# H09R0.net
KiCad netlist of a schematic drawn in EAGLE
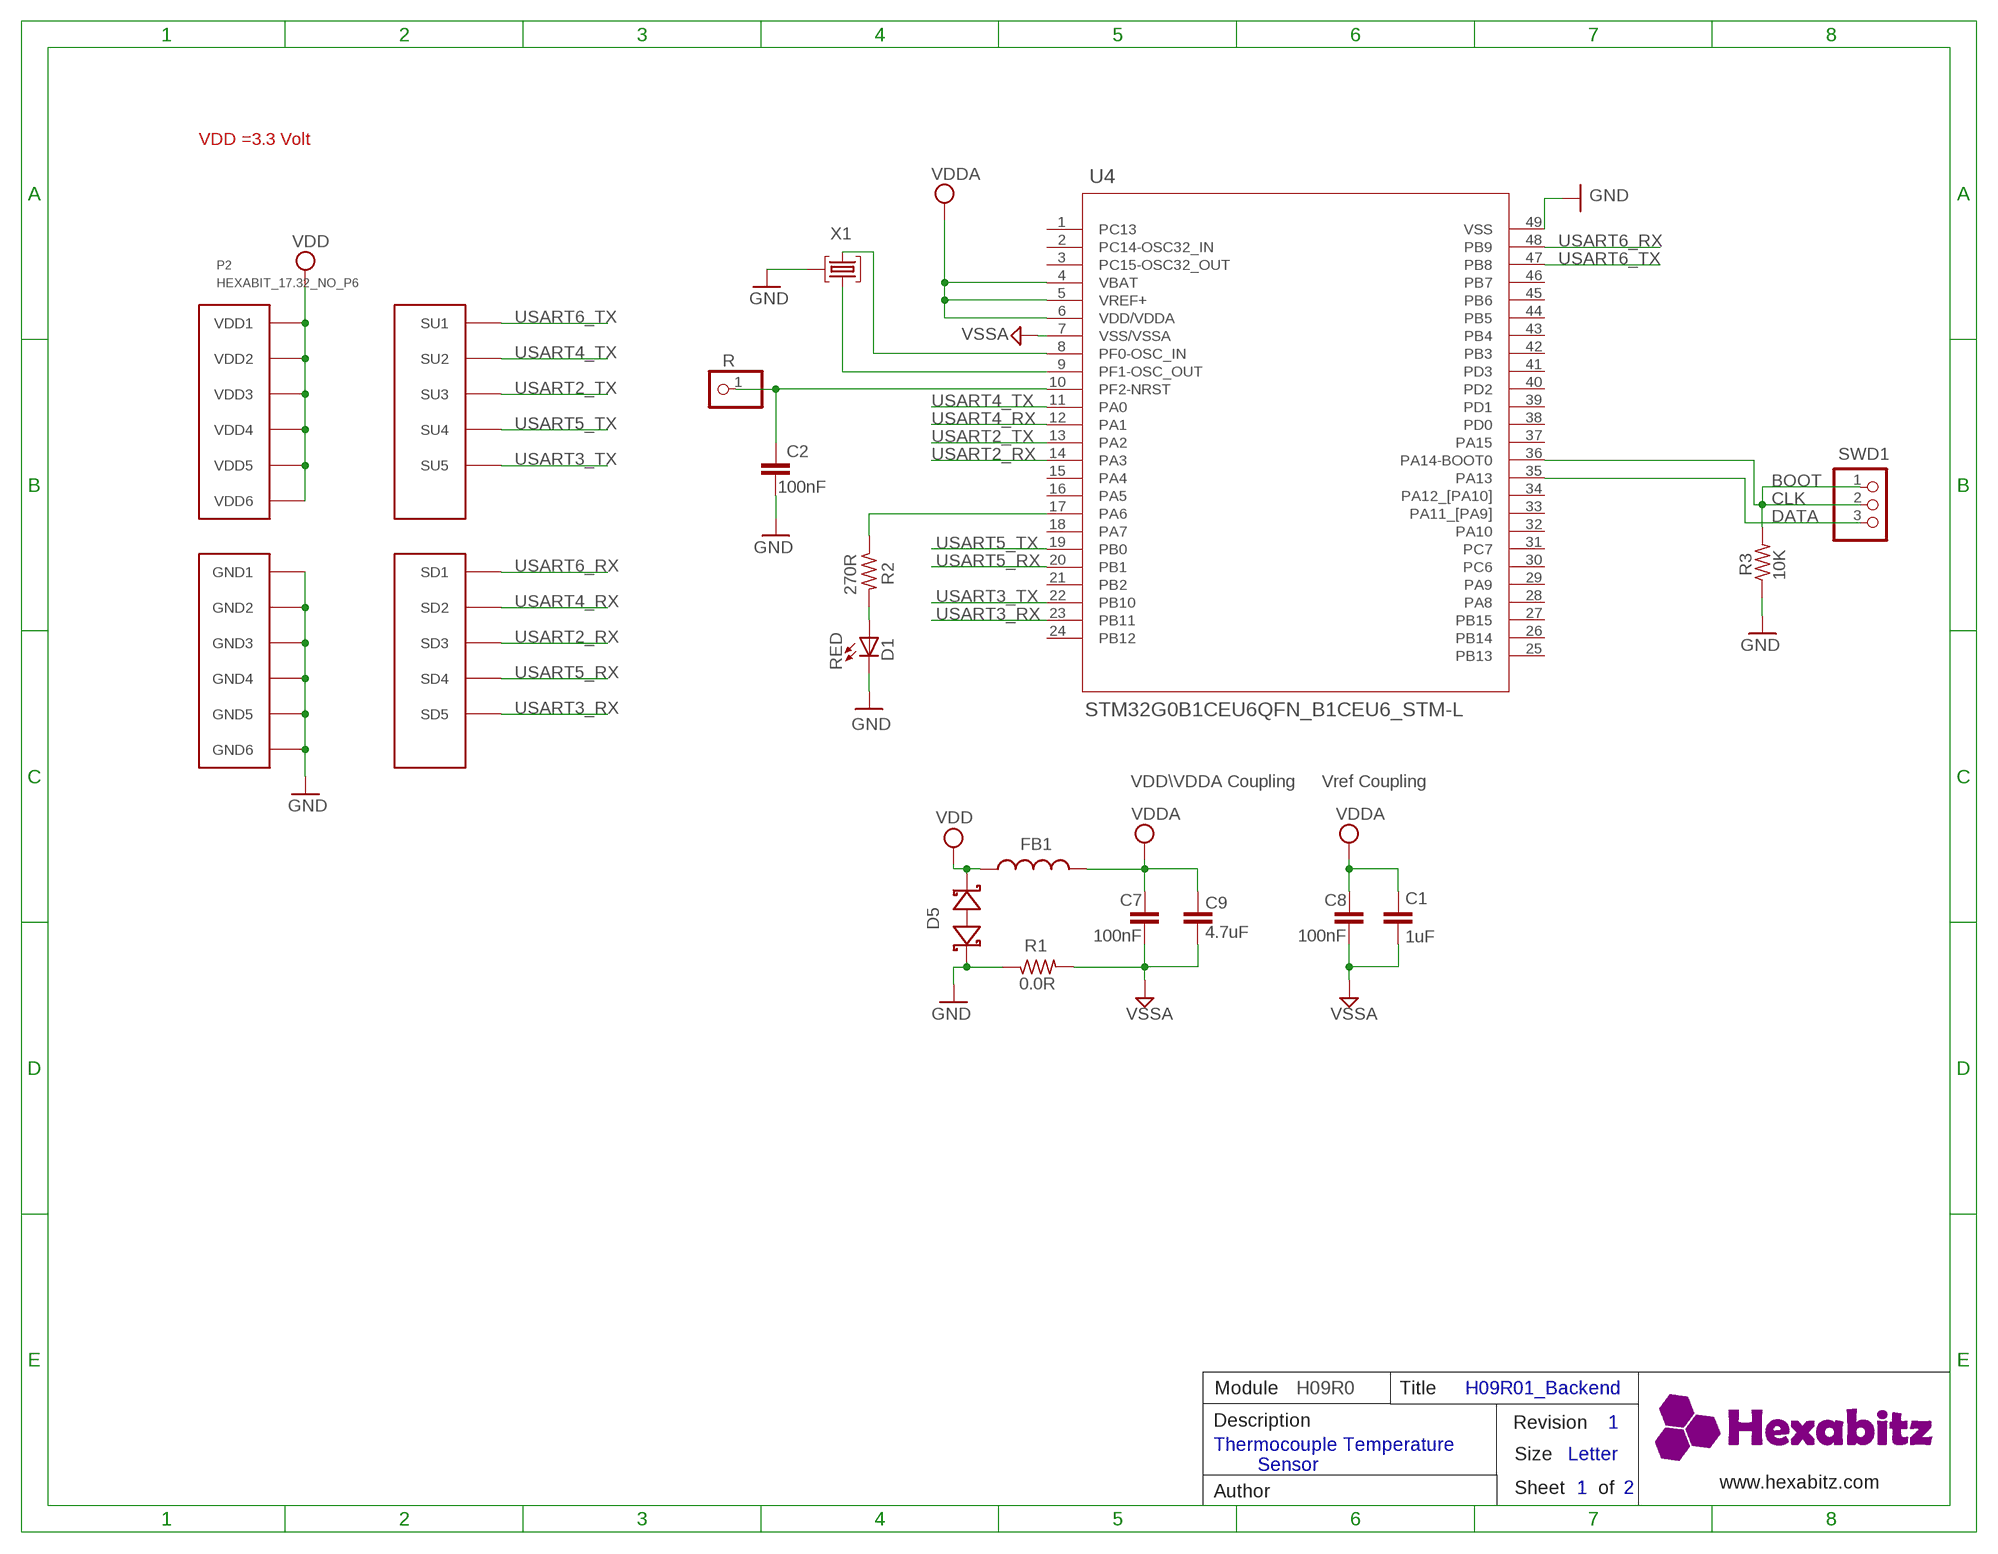
[diagram p0: schematic, sheet 1]
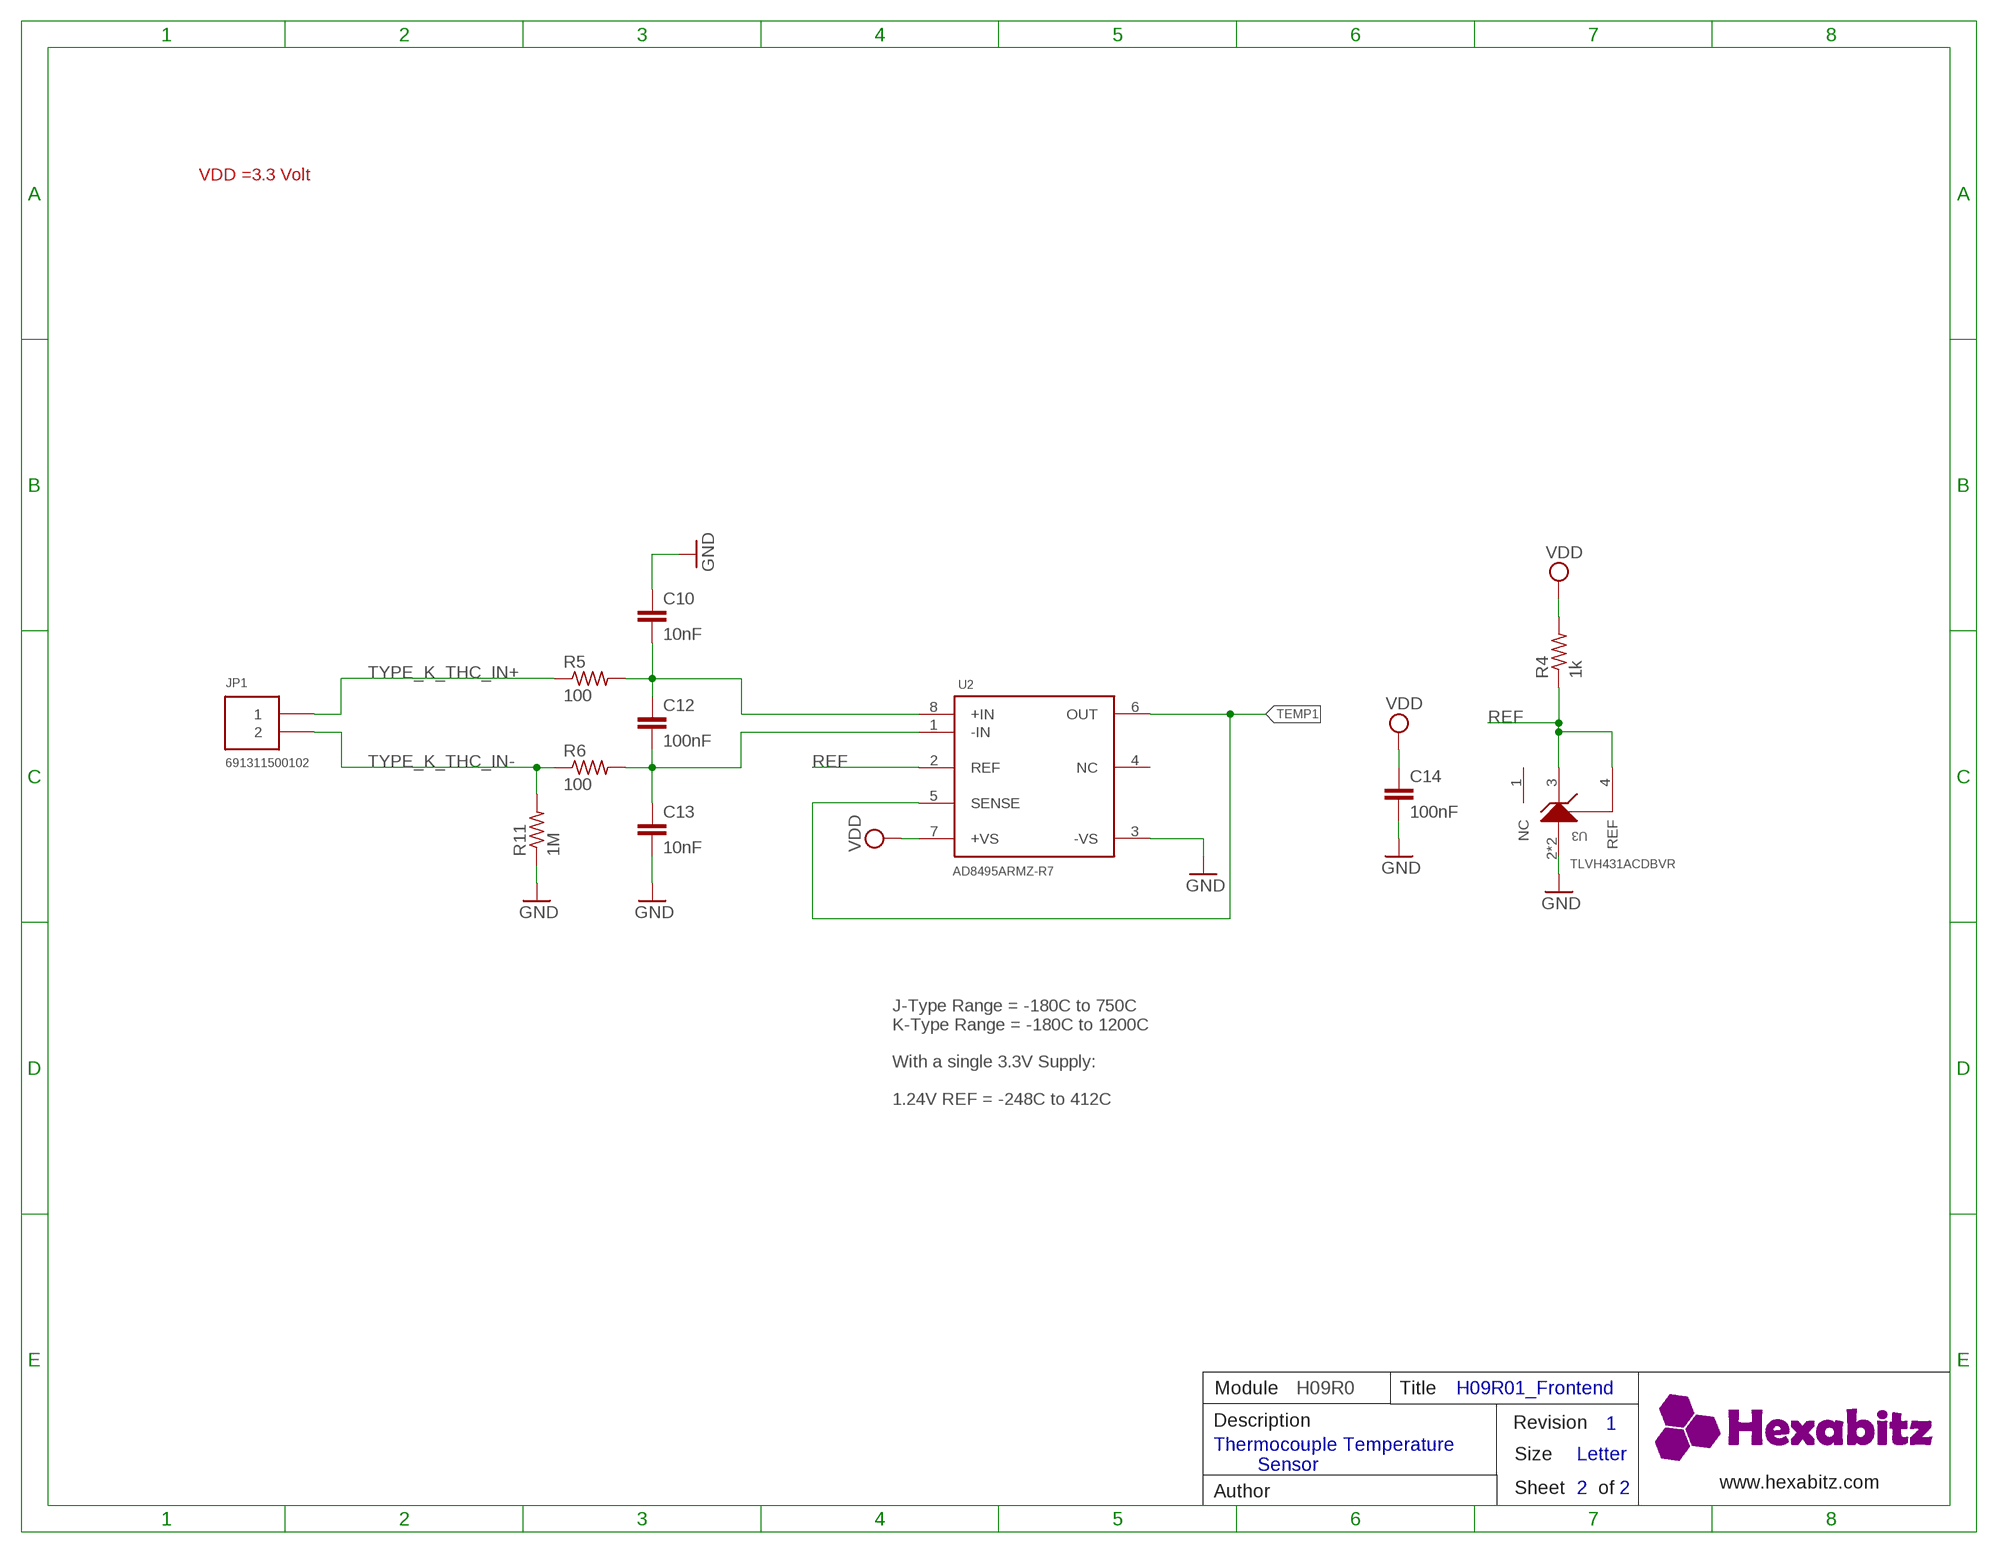
[diagram p1: schematic, sheet 2]

(export (version "E")
  (design (tool "Eeschema 10.0.6"))
  (components
    (comp (ref "C1")
      (value "1uF")
      (footprint "eagle-import:C-0805")
      (libsource (lib "eagle-import") (part "C-0805"))
    )
    (comp (ref "C2")
      (value "100nF")
      (footprint "eagle-import:C-0603")
      (libsource (lib "eagle-import") (part "C-0603"))
    )
    (comp (ref "C7")
      (value "100nF")
      (footprint "eagle-import:C-0603")
      (libsource (lib "eagle-import") (part "C-0603"))
    )
    (comp (ref "C8")
      (value "100nF")
      (footprint "eagle-import:C-0603")
      (libsource (lib "eagle-import") (part "C-0603"))
    )
    (comp (ref "C9")
      (value "4.7uF")
      (footprint "eagle-import:C-0805")
      (libsource (lib "eagle-import") (part "C-0805"))
    )
    (comp (ref "D1")
      (value "RED")
      (footprint "eagle-import:VLMS1300-GS08")
      (fields
        (field (name "MPN") "VLMS1300-GS08")
        (field (name "MFN") "Vishay")
        (field (name "MPN_1") "VLMS1300-GS08")
        (field (name "OCTOPART_URL") "https://octopart.com/vlms1300-gs08-vishay-21709201?r=sp&s=_gcP4_q8T1SC6PJQPTQ9yA")
      )
      (libsource (lib "eagle-import") (part "VLMS1300-GS08"))
    )
    (comp (ref "D5")
      (value "BOURNS_CDSOD323-T03SCBOURNS_CDSOD323-T03SC_0_0")
      (footprint "eagle-import:BOURNS_CDSOD323-T03SC_0")
      (fields (field (name "MPN") "CDSOD323-T03SC"))
      (libsource (lib "eagle-import") (part "BOURNS_CDSOD323-T03SCBOURNS_CDSOD323-T03SC_0_0"))
    )
    (comp (ref "FB1")
      (value "FB-TDK_MMZ1608Y300B")
      (footprint "eagle-import:FB-0603")
      (fields
        (field (name "MFN") "TDK ")
        (field (name "MPN") "MMZ1608Y300B")
        (field (name "OCTOPART_URL") "https://octopart.com/mmz1608y300b-tdk-368280?r=sp&s=cd9_2ZEqQ9q9UNBuQgHAiA")
      )
      (libsource (lib "eagle-import") (part "FB-0603"))
    )
    (comp (ref "P2")
      (value "HEXABIT_17.32_NO_P6")
      (footprint "eagle-import:HEXABIT_17.32_NO_P6")
      (libsource (lib "eagle-import") (part "HEXABIT_?_NO_P617.32"))
    )
    (comp (ref "R")
      (value "R")
      (footprint "eagle-import:1X01")
      (fields (field (name "MPN") "87227-1"))
      (libsource (lib "eagle-import") (part "PINHD-1X1"))
    )
    (comp (ref "R1")
      (value "0.0R")
      (footprint "eagle-import:R-0603")
      (fields
        (field (name "MFN") "Yageo")
        (field (name "MPN") "RC0603JR-070RL")
        (field (name "OCTOPART_URL") "https://octopart.com/rc0603jr-070rl-yageo-1241539?r=sp&s=X2NteqRjRNWrnx42Y0aliA")
        (field (name "RESISTANCE") "0.0 Ohm")
      )
      (libsource (lib "eagle-import") (part "R-0603"))
    )
    (comp (ref "R2")
      (value "270R")
      (footprint "eagle-import:R-0603")
      (libsource (lib "eagle-import") (part "R-0603"))
    )
    (comp (ref "R3")
      (value "10K")
      (footprint "eagle-import:R-0603")
      (libsource (lib "eagle-import") (part "R-0603"))
    )
    (comp (ref "SWD1")
      (value "PINHD-1X3")
      (footprint "eagle-import:1X03")
      (libsource (lib "eagle-import") (part "PINHD-1X3"))
    )
    (comp (ref "U4")
      (value "STM32G0B1CEU6QFN_B1CEU6_STM-L")
      (footprint "eagle-import:QFN_B1CEU6_STM-L")
      (fields
        (field (name "MANUFACTURER_PART_NUMBER") "STM32G0B1CEU6")
        (field (name "SPICEPREFIX") "X")
        (field (name "COPYRIGHT") "Copyright (C) 2021 Ultra Librarian. All rights reserved.")
      )
      (libsource (lib "eagle-import") (part "STM32G0B1CEU6QFN_B1CEU6_STM-L"))
    )
    (comp (ref "X1")
      (value "XTALL_CSTCE8M00G52")
      (footprint "eagle-import:XTALL_CSTCE8M00G52")
      (fields (field (name "MPN") "CSTCE8M00G52Z-R0"))
      (libsource (lib "eagle-import") (part "XTALL_CSTCE8M00G52"))
    )
    (comp (ref "C10")
      (value "10nF")
      (footprint "eagle-import:C-0603")
      (fields
        (field (name "CAPACITANCE") "10nF")
        (field (name "MFN") "KEMET")
        (field (name "MPN") "C0603C103K5RACTU")
        (field (name "OCTOPART_URL") "https://octopart.com/c0603c103k5ractu-kemet-133094?r=sp&s=R_iPBxLnSmGqhkU2rIMFpg")
        (field (name "TOLERANCE") "10%")
        (field (name "VOLTAGE_RATING") "50V")
      )
      (libsource (lib "eagle-import") (part "C-0603"))
    )
    (comp (ref "C12")
      (value "100nF")
      (footprint "eagle-import:C-0603")
      (fields
        (field (name "CAPACITANCE") "100nF")
        (field (name "MFN") "KEMET")
        (field (name "MPN") "C0603C104K8RACTU")
        (field (name "OCTOPART_URL") "https://octopart.com/c0603c104k8ractu-kemet-145075?r=sp&s=9bS9ASSwSEqMCE9KBEQZ0g")
        (field (name "TOLERANCE") "10%")
        (field (name "VOLTAGE_RATING") "10V")
      )
      (libsource (lib "eagle-import") (part "C-0603"))
    )
    (comp (ref "C13")
      (value "10nF")
      (footprint "eagle-import:C-0603")
      (fields
        (field (name "CAPACITANCE") "10nF")
        (field (name "MFN") "KEMET")
        (field (name "MPN") "C0603C103K5RACTU")
        (field (name "OCTOPART_URL") "https://octopart.com/c0603c103k5ractu-kemet-133094?r=sp&s=R_iPBxLnSmGqhkU2rIMFpg")
        (field (name "TOLERANCE") "10%")
        (field (name "VOLTAGE_RATING") "50V")
      )
      (libsource (lib "eagle-import") (part "C-0603"))
    )
    (comp (ref "C14")
      (value "100nF")
      (footprint "eagle-import:C-0603")
      (fields
        (field (name "CAPACITANCE") "100nF")
        (field (name "MFN") "KEMET")
        (field (name "MPN") "C0603C104K8RACTU")
        (field (name "OCTOPART_URL") "https://octopart.com/c0603c104k8ractu-kemet-145075?r=sp&s=9bS9ASSwSEqMCE9KBEQZ0g")
        (field (name "TOLERANCE") "10%")
        (field (name "VOLTAGE_RATING") "10V")
      )
      (libsource (lib "eagle-import") (part "C-0603"))
    )
    (comp (ref "JP1")
      (value "691311500102")
      (footprint "eagle-import:1546111-2")
      (fields (field (name "MPN") "1546111-2"))
      (libsource (lib "eagle-import") (part "1546111-2"))
    )
    (comp (ref "R4")
      (value "1k")
      (footprint "eagle-import:R-0402")
      (fields
        (field (name "MFN") "Yageo")
        (field (name "MPN") "RC0402FR-071KL")
        (field (name "OCTOPART_URL") "https://octopart.com/search?q=RC0402FR-071KL&start=0")
        (field (name "RESISTANCE") "1k")
        (field (name "TOLERANCE") "1%")
      )
      (libsource (lib "eagle-import") (part "R-0402"))
    )
    (comp (ref "R5")
      (value "100")
      (footprint "eagle-import:R-0402")
      (fields
        (field (name "MFN") "Yageo")
        (field (name "MPN") "RC0402FR-07100RL")
        (field (name "OCTOPART_URL") "https://octopart.com/search?q=RC0402FR-07100RL&start=0")
        (field (name "RESISTANCE") "100")
        (field (name "TOLERANCE") "1%")
      )
      (libsource (lib "eagle-import") (part "R-0402"))
    )
    (comp (ref "R6")
      (value "100")
      (footprint "eagle-import:R-0402")
      (fields
        (field (name "MFN") "Yageo")
        (field (name "MPN") "RC0402FR-07100RL")
        (field (name "OCTOPART_URL") "https://octopart.com/search?q=RC0402FR-07100RL&start=0")
        (field (name "RESISTANCE") "100")
        (field (name "TOLERANCE") "1%")
      )
      (libsource (lib "eagle-import") (part "R-0402"))
    )
    (comp (ref "R11")
      (value "1M")
      (footprint "eagle-import:R-0402")
      (fields
        (field (name "MFN") "Yageo")
        (field (name "MPN") "RC0402FR-071ML")
        (field (name "OCTOPART_URL") "https://octopart.com/search?q=RC0402FR-071ML&start=0")
        (field (name "RESISTANCE") "1M")
        (field (name "TOLERANCE") "1%")
      )
      (libsource (lib "eagle-import") (part "R-0402"))
    )
    (comp (ref "U2")
      (value "AD8495ARMZ-R7")
      (footprint "eagle-import:AD8495ARMZ")
      (fields (field (name "MFG") "Analog Devices"))
      (libsource (lib "eagle-import") (part "AD8495ARMZ"))
    )
    (comp (ref "U3")
      (value "TLVH431ACDBVR")
      (footprint "eagle-import:TLVH431ACDBVR")
      (libsource (lib "eagle-import") (part "TLVH431ACDBVR"))
    )
  )
  (nets
    (net (code "1") (name "CLK") (class "Default")
      (node (ref "R3") (pin "2") (pinfunction "2_2") (pintype "passive"))
      (node (ref "SWD1") (pin "1") (pinfunction "1_1") (pintype "passive"))
      (node (ref "SWD1") (pin "2") (pinfunction "2_2") (pintype "passive"))
      (node (ref "U4") (pin "36") (pinfunction "PA14-BOOT0_36") (pintype "bidirectional"))
    )
    (net (code "2") (name "DATA") (class "Default")
      (node (ref "SWD1") (pin "3") (pinfunction "3_3") (pintype "passive"))
      (node (ref "U4") (pin "35") (pinfunction "PA13_35") (pintype "bidirectional"))
    )
    (net (code "3") (name "GND") (class "Default")
      (node (ref "C10") (pin "1") (pinfunction "1_1") (pintype "passive"))
      (node (ref "C13") (pin "2") (pinfunction "2_2") (pintype "passive"))
      (node (ref "C14") (pin "2") (pinfunction "2_2") (pintype "passive"))
      (node (ref "C2") (pin "2") (pinfunction "2_2") (pintype "passive"))
      (node (ref "D1") (pin "C") (pinfunction "C_C") (pintype "passive"))
      (node (ref "D5") (pin "1") (pinfunction "A_1") (pintype "passive"))
      (node (ref "P2") (pin "PAD_PD10") (pinfunction "GND4_PAD_PD10") (pintype "power_in"))
      (node (ref "P2") (pin "PAD_PD11") (pinfunction "GND5_PAD_PD11") (pintype "power_in"))
      (node (ref "P2") (pin "PAD_PD12") (pinfunction "GND6_PAD_PD12") (pintype "power_in"))
      (node (ref "P2") (pin "PAD_PD7") (pinfunction "GND1_PAD_PD7") (pintype "power_in"))
      (node (ref "P2") (pin "PAD_PD8") (pinfunction "GND2_PAD_PD8") (pintype "power_in"))
      (node (ref "P2") (pin "PAD_PD9") (pinfunction "GND3_PAD_PD9") (pintype "power_in"))
      (node (ref "R1") (pin "1") (pinfunction "1_1") (pintype "passive"))
      (node (ref "R11") (pin "1") (pinfunction "1_1") (pintype "passive"))
      (node (ref "R3") (pin "1") (pinfunction "1_1") (pintype "passive"))
      (node (ref "U2") (pin "3") (pinfunction "-VS_3") (pintype "power_in"))
      (node (ref "U3") (pin "2") (pinfunction "ANODE_2") (pintype "input"))
      (node (ref "U3") (pin "5") (pinfunction "ANODE_5") (pintype "input"))
      (node (ref "U4") (pin "49") (pinfunction "VSS_49") (pintype "passive"))
      (node (ref "X1") (pin "P$2") (pinfunction "2_P$2") (pintype "passive"))
    )
    (net (code "4") (name "Net-(D1-PadA)") (class "Default")
      (node (ref "D1") (pin "A") (pinfunction "A_A") (pintype "passive"))
      (node (ref "R2") (pin "2") (pinfunction "2_2") (pintype "passive"))
    )
    (net (code "5") (name "Net-(U2-+IN)") (class "Default")
      (node (ref "C10") (pin "2") (pinfunction "2_2") (pintype "passive"))
      (node (ref "C12") (pin "1") (pinfunction "1_1") (pintype "passive"))
      (node (ref "R5") (pin "2") (pinfunction "2_2") (pintype "passive"))
      (node (ref "U2") (pin "8") (pinfunction "+IN_8") (pintype "bidirectional"))
    )
    (net (code "6") (name "Net-(U2--IN)") (class "Default")
      (node (ref "C12") (pin "2") (pinfunction "2_2") (pintype "passive"))
      (node (ref "C13") (pin "1") (pinfunction "1_1") (pintype "passive"))
      (node (ref "R6") (pin "2") (pinfunction "2_2") (pintype "passive"))
      (node (ref "U2") (pin "1") (pinfunction "-IN_1") (pintype "bidirectional"))
    )
    (net (code "7") (name "Net-(U4-PA6)") (class "Default")
      (node (ref "R2") (pin "1") (pinfunction "1_1") (pintype "passive"))
      (node (ref "U4") (pin "17") (pinfunction "PA6_17") (pintype "bidirectional"))
    )
    (net (code "8") (name "Net-(U4-PF0-OSC_IN)") (class "Default")
      (node (ref "U4") (pin "8") (pinfunction "PF0-OSC_IN_8") (pintype "bidirectional"))
      (node (ref "X1") (pin "P$3") (pinfunction "3_P$3") (pintype "passive"))
    )
    (net (code "9") (name "Net-(U4-PF1-OSC_OUT)") (class "Default")
      (node (ref "U4") (pin "9") (pinfunction "PF1-OSC_OUT_9") (pintype "output"))
      (node (ref "X1") (pin "P$1") (pinfunction "1_P$1") (pintype "passive"))
    )
    (net (code "10") (name "Net-(U4-PF2-NRST)") (class "Default")
      (node (ref "C2") (pin "1") (pinfunction "1_1") (pintype "passive"))
      (node (ref "R") (pin "1") (pinfunction "1_1") (pintype "passive"))
      (node (ref "U4") (pin "10") (pinfunction "PF2-NRST_10") (pintype "bidirectional"))
    )
    (net (code "11") (name "REF") (class "Default")
      (node (ref "R4") (pin "1") (pinfunction "1_1") (pintype "passive"))
      (node (ref "U2") (pin "2") (pinfunction "REF_2") (pintype "bidirectional"))
      (node (ref "U3") (pin "3") (pinfunction "CATHODE_3") (pintype "output"))
      (node (ref "U3") (pin "4") (pinfunction "REF_4") (pintype "input"))
    )
    (net (code "12") (name "TEMP1") (class "Default")
      (node (ref "U2") (pin "5") (pinfunction "SENSE_5") (pintype "bidirectional"))
      (node (ref "U2") (pin "6") (pinfunction "OUT_6") (pintype "output"))
    )
    (net (code "13") (name "TYPE_K_THC_IN+") (class "Default")
      (node (ref "JP1") (pin "1") (pinfunction "1_1") (pintype "power_in"))
      (node (ref "R5") (pin "1") (pinfunction "1_1") (pintype "passive"))
    )
    (net (code "14") (name "TYPE_K_THC_IN-") (class "Default")
      (node (ref "JP1") (pin "2") (pinfunction "2_2") (pintype "power_in"))
      (node (ref "R11") (pin "2") (pinfunction "2_2") (pintype "passive"))
      (node (ref "R6") (pin "1") (pinfunction "1_1") (pintype "passive"))
    )
    (net (code "15") (name "USART2_RX") (class "Default")
      (node (ref "P2") (pin "PAD_PD3") (pinfunction "SD3_PAD_PD3") (pintype "bidirectional"))
      (node (ref "U4") (pin "14") (pinfunction "PA3_14") (pintype "bidirectional"))
    )
    (net (code "16") (name "USART2_TX") (class "Default")
      (node (ref "P2") (pin "PAD_PU3") (pinfunction "SU3_PAD_PU3") (pintype "bidirectional"))
      (node (ref "U4") (pin "13") (pinfunction "PA2_13") (pintype "bidirectional"))
    )
    (net (code "17") (name "USART3_RX") (class "Default")
      (node (ref "P2") (pin "PAD_PD5") (pinfunction "SD5_PAD_PD5") (pintype "bidirectional"))
      (node (ref "U4") (pin "23") (pinfunction "PB11_23") (pintype "bidirectional"))
    )
    (net (code "18") (name "USART3_TX") (class "Default")
      (node (ref "P2") (pin "PAD_PU5") (pinfunction "SU5_PAD_PU5") (pintype "bidirectional"))
      (node (ref "U4") (pin "22") (pinfunction "PB10_22") (pintype "bidirectional"))
    )
    (net (code "19") (name "USART4_RX") (class "Default")
      (node (ref "P2") (pin "PAD_PD2") (pinfunction "SD2_PAD_PD2") (pintype "bidirectional"))
      (node (ref "U4") (pin "12") (pinfunction "PA1_12") (pintype "bidirectional"))
    )
    (net (code "20") (name "USART4_TX") (class "Default")
      (node (ref "P2") (pin "PAD_PU2") (pinfunction "SU2_PAD_PU2") (pintype "bidirectional"))
      (node (ref "U4") (pin "11") (pinfunction "PA0_11") (pintype "bidirectional"))
    )
    (net (code "21") (name "USART5_RX") (class "Default")
      (node (ref "P2") (pin "PAD_PD4") (pinfunction "SD4_PAD_PD4") (pintype "bidirectional"))
      (node (ref "U4") (pin "20") (pinfunction "PB1_20") (pintype "bidirectional"))
    )
    (net (code "22") (name "USART5_TX") (class "Default")
      (node (ref "P2") (pin "PAD_PU4") (pinfunction "SU4_PAD_PU4") (pintype "bidirectional"))
      (node (ref "U4") (pin "19") (pinfunction "PB0_19") (pintype "bidirectional"))
    )
    (net (code "23") (name "USART6_RX") (class "Default")
      (node (ref "P2") (pin "PAD_PD1") (pinfunction "SD1_PAD_PD1") (pintype "bidirectional"))
      (node (ref "U4") (pin "48") (pinfunction "PB9_48") (pintype "bidirectional"))
    )
    (net (code "24") (name "USART6_TX") (class "Default")
      (node (ref "P2") (pin "PAD_PU1") (pinfunction "SU1_PAD_PU1") (pintype "bidirectional"))
      (node (ref "U4") (pin "47") (pinfunction "PB8_47") (pintype "bidirectional"))
    )
    (net (code "25") (name "VDD") (class "Default")
      (node (ref "C14") (pin "1") (pinfunction "1_1") (pintype "passive"))
      (node (ref "D5") (pin "2") (pinfunction "C_2") (pintype "passive"))
      (node (ref "FB1") (pin "2") (pinfunction "2_2") (pintype "passive"))
      (node (ref "P2") (pin "PAD_PU10") (pinfunction "VDD4_PAD_PU10") (pintype "power_in"))
      (node (ref "P2") (pin "PAD_PU11") (pinfunction "VDD5_PAD_PU11") (pintype "power_in"))
      (node (ref "P2") (pin "PAD_PU12") (pinfunction "VDD6_PAD_PU12") (pintype "power_in"))
      (node (ref "P2") (pin "PAD_PU7") (pinfunction "VDD1_PAD_PU7") (pintype "power_in"))
      (node (ref "P2") (pin "PAD_PU8") (pinfunction "VDD2_PAD_PU8") (pintype "power_in"))
      (node (ref "P2") (pin "PAD_PU9") (pinfunction "VDD3_PAD_PU9") (pintype "power_in"))
      (node (ref "R4") (pin "2") (pinfunction "2_2") (pintype "passive"))
      (node (ref "U2") (pin "7") (pinfunction "+VS_7") (pintype "power_in"))
    )
    (net (code "26") (name "VDDA") (class "Default")
      (node (ref "C1") (pin "1") (pinfunction "1_1") (pintype "passive"))
      (node (ref "C7") (pin "1") (pinfunction "1_1") (pintype "passive"))
      (node (ref "C8") (pin "1") (pinfunction "1_1") (pintype "passive"))
      (node (ref "C9") (pin "1") (pinfunction "1_1") (pintype "passive"))
      (node (ref "FB1") (pin "1") (pinfunction "1_1") (pintype "passive"))
      (node (ref "U4") (pin "4") (pinfunction "VBAT_4") (pintype "passive"))
      (node (ref "U4") (pin "5") (pinfunction "VREF+_5") (pintype "power_in"))
      (node (ref "U4") (pin "6") (pinfunction "VDD/VDDA_6") (pintype "power_in"))
    )
    (net (code "27") (name "VSSA") (class "Default")
      (node (ref "C1") (pin "2") (pinfunction "2_2") (pintype "passive"))
      (node (ref "C7") (pin "2") (pinfunction "2_2") (pintype "passive"))
      (node (ref "C8") (pin "2") (pinfunction "2_2") (pintype "passive"))
      (node (ref "C9") (pin "2") (pinfunction "2_2") (pintype "passive"))
      (node (ref "R1") (pin "2") (pinfunction "2_2") (pintype "passive"))
      (node (ref "U4") (pin "7") (pinfunction "VSS/VSSA_7") (pintype "passive"))
    )
    (net (code "28") (name "unconnected-(U2-NC-Pad4)") (class "Default")
      (node (ref "U2") (pin "4") (pinfunction "NC_4") (pintype "no_connect"))
    )
    (net (code "29") (name "unconnected-(U3-NC-Pad1)") (class "Default")
      (node (ref "U3") (pin "1") (pinfunction "NC_1") (pintype "no_connect"))
    )
    (net (code "30") (name "unconnected-(U4-PA4-Pad15)") (class "Default")
      (node (ref "U4") (pin "15") (pinfunction "PA4_15") (pintype "bidirectional"))
    )
    (net (code "31") (name "unconnected-(U4-PA5-Pad16)") (class "Default")
      (node (ref "U4") (pin "16") (pinfunction "PA5_16") (pintype "bidirectional"))
    )
    (net (code "32") (name "unconnected-(U4-PA7-Pad18)") (class "Default")
      (node (ref "U4") (pin "18") (pinfunction "PA7_18") (pintype "bidirectional"))
    )
    (net (code "33") (name "unconnected-(U4-PA8-Pad28)") (class "Default")
      (node (ref "U4") (pin "28") (pinfunction "PA8_28") (pintype "bidirectional"))
    )
    (net (code "34") (name "unconnected-(U4-PA9-Pad29)") (class "Default")
      (node (ref "U4") (pin "29") (pinfunction "PA9_29") (pintype "bidirectional"))
    )
    (net (code "35") (name "unconnected-(U4-PA10-Pad32)") (class "Default")
      (node (ref "U4") (pin "32") (pinfunction "PA10_32") (pintype "bidirectional"))
    )
    (net (code "36") (name "unconnected-(U4-PA11_[PA9]-Pad33)") (class "Default")
      (node (ref "U4") (pin "33") (pinfunction "PA11_[PA9]_33") (pintype "bidirectional"))
    )
    (net (code "37") (name "unconnected-(U4-PA12_[PA10]-Pad34)") (class "Default")
      (node (ref "U4") (pin "34") (pinfunction "PA12_[PA10]_34") (pintype "bidirectional"))
    )
    (net (code "38") (name "unconnected-(U4-PA15-Pad37)") (class "Default")
      (node (ref "U4") (pin "37") (pinfunction "PA15_37") (pintype "bidirectional"))
    )
    (net (code "39") (name "unconnected-(U4-PB2-Pad21)") (class "Default")
      (node (ref "U4") (pin "21") (pinfunction "PB2_21") (pintype "bidirectional"))
    )
    (net (code "40") (name "unconnected-(U4-PB3-Pad42)") (class "Default")
      (node (ref "U4") (pin "42") (pinfunction "PB3_42") (pintype "bidirectional"))
    )
    (net (code "41") (name "unconnected-(U4-PB4-Pad43)") (class "Default")
      (node (ref "U4") (pin "43") (pinfunction "PB4_43") (pintype "bidirectional"))
    )
    (net (code "42") (name "unconnected-(U4-PB5-Pad44)") (class "Default")
      (node (ref "U4") (pin "44") (pinfunction "PB5_44") (pintype "bidirectional"))
    )
    (net (code "43") (name "unconnected-(U4-PB6-Pad45)") (class "Default")
      (node (ref "U4") (pin "45") (pinfunction "PB6_45") (pintype "bidirectional"))
    )
    (net (code "44") (name "unconnected-(U4-PB7-Pad46)") (class "Default")
      (node (ref "U4") (pin "46") (pinfunction "PB7_46") (pintype "bidirectional"))
    )
    (net (code "45") (name "unconnected-(U4-PB12-Pad24)") (class "Default")
      (node (ref "U4") (pin "24") (pinfunction "PB12_24") (pintype "bidirectional"))
    )
    (net (code "46") (name "unconnected-(U4-PB13-Pad25)") (class "Default")
      (node (ref "U4") (pin "25") (pinfunction "PB13_25") (pintype "bidirectional"))
    )
    (net (code "47") (name "unconnected-(U4-PB14-Pad26)") (class "Default")
      (node (ref "U4") (pin "26") (pinfunction "PB14_26") (pintype "bidirectional"))
    )
    (net (code "48") (name "unconnected-(U4-PB15-Pad27)") (class "Default")
      (node (ref "U4") (pin "27") (pinfunction "PB15_27") (pintype "bidirectional"))
    )
    (net (code "49") (name "unconnected-(U4-PC6-Pad30)") (class "Default")
      (node (ref "U4") (pin "30") (pinfunction "PC6_30") (pintype "bidirectional"))
    )
    (net (code "50") (name "unconnected-(U4-PC7-Pad31)") (class "Default")
      (node (ref "U4") (pin "31") (pinfunction "PC7_31") (pintype "bidirectional"))
    )
    (net (code "51") (name "unconnected-(U4-PC13-Pad1)") (class "Default")
      (node (ref "U4") (pin "1") (pinfunction "PC13_1") (pintype "bidirectional"))
    )
    (net (code "52") (name "unconnected-(U4-PC14-OSC32_IN-Pad2)") (class "Default")
      (node (ref "U4") (pin "2") (pinfunction "PC14-OSC32_IN_2") (pintype "bidirectional"))
    )
    (net (code "53") (name "unconnected-(U4-PC15-OSC32_OUT-Pad3)") (class "Default")
      (node (ref "U4") (pin "3") (pinfunction "PC15-OSC32_OUT_3") (pintype "output"))
    )
    (net (code "54") (name "unconnected-(U4-PD0-Pad38)") (class "Default")
      (node (ref "U4") (pin "38") (pinfunction "PD0_38") (pintype "bidirectional"))
    )
    (net (code "55") (name "unconnected-(U4-PD1-Pad39)") (class "Default")
      (node (ref "U4") (pin "39") (pinfunction "PD1_39") (pintype "bidirectional"))
    )
    (net (code "56") (name "unconnected-(U4-PD2-Pad40)") (class "Default")
      (node (ref "U4") (pin "40") (pinfunction "PD2_40") (pintype "bidirectional"))
    )
    (net (code "57") (name "unconnected-(U4-PD3-Pad41)") (class "Default")
      (node (ref "U4") (pin "41") (pinfunction "PD3_41") (pintype "bidirectional"))
    )
  )
)
